# PC_JTAGInterface.net
KiCad netlist of a schematic drawn in Altium Designer
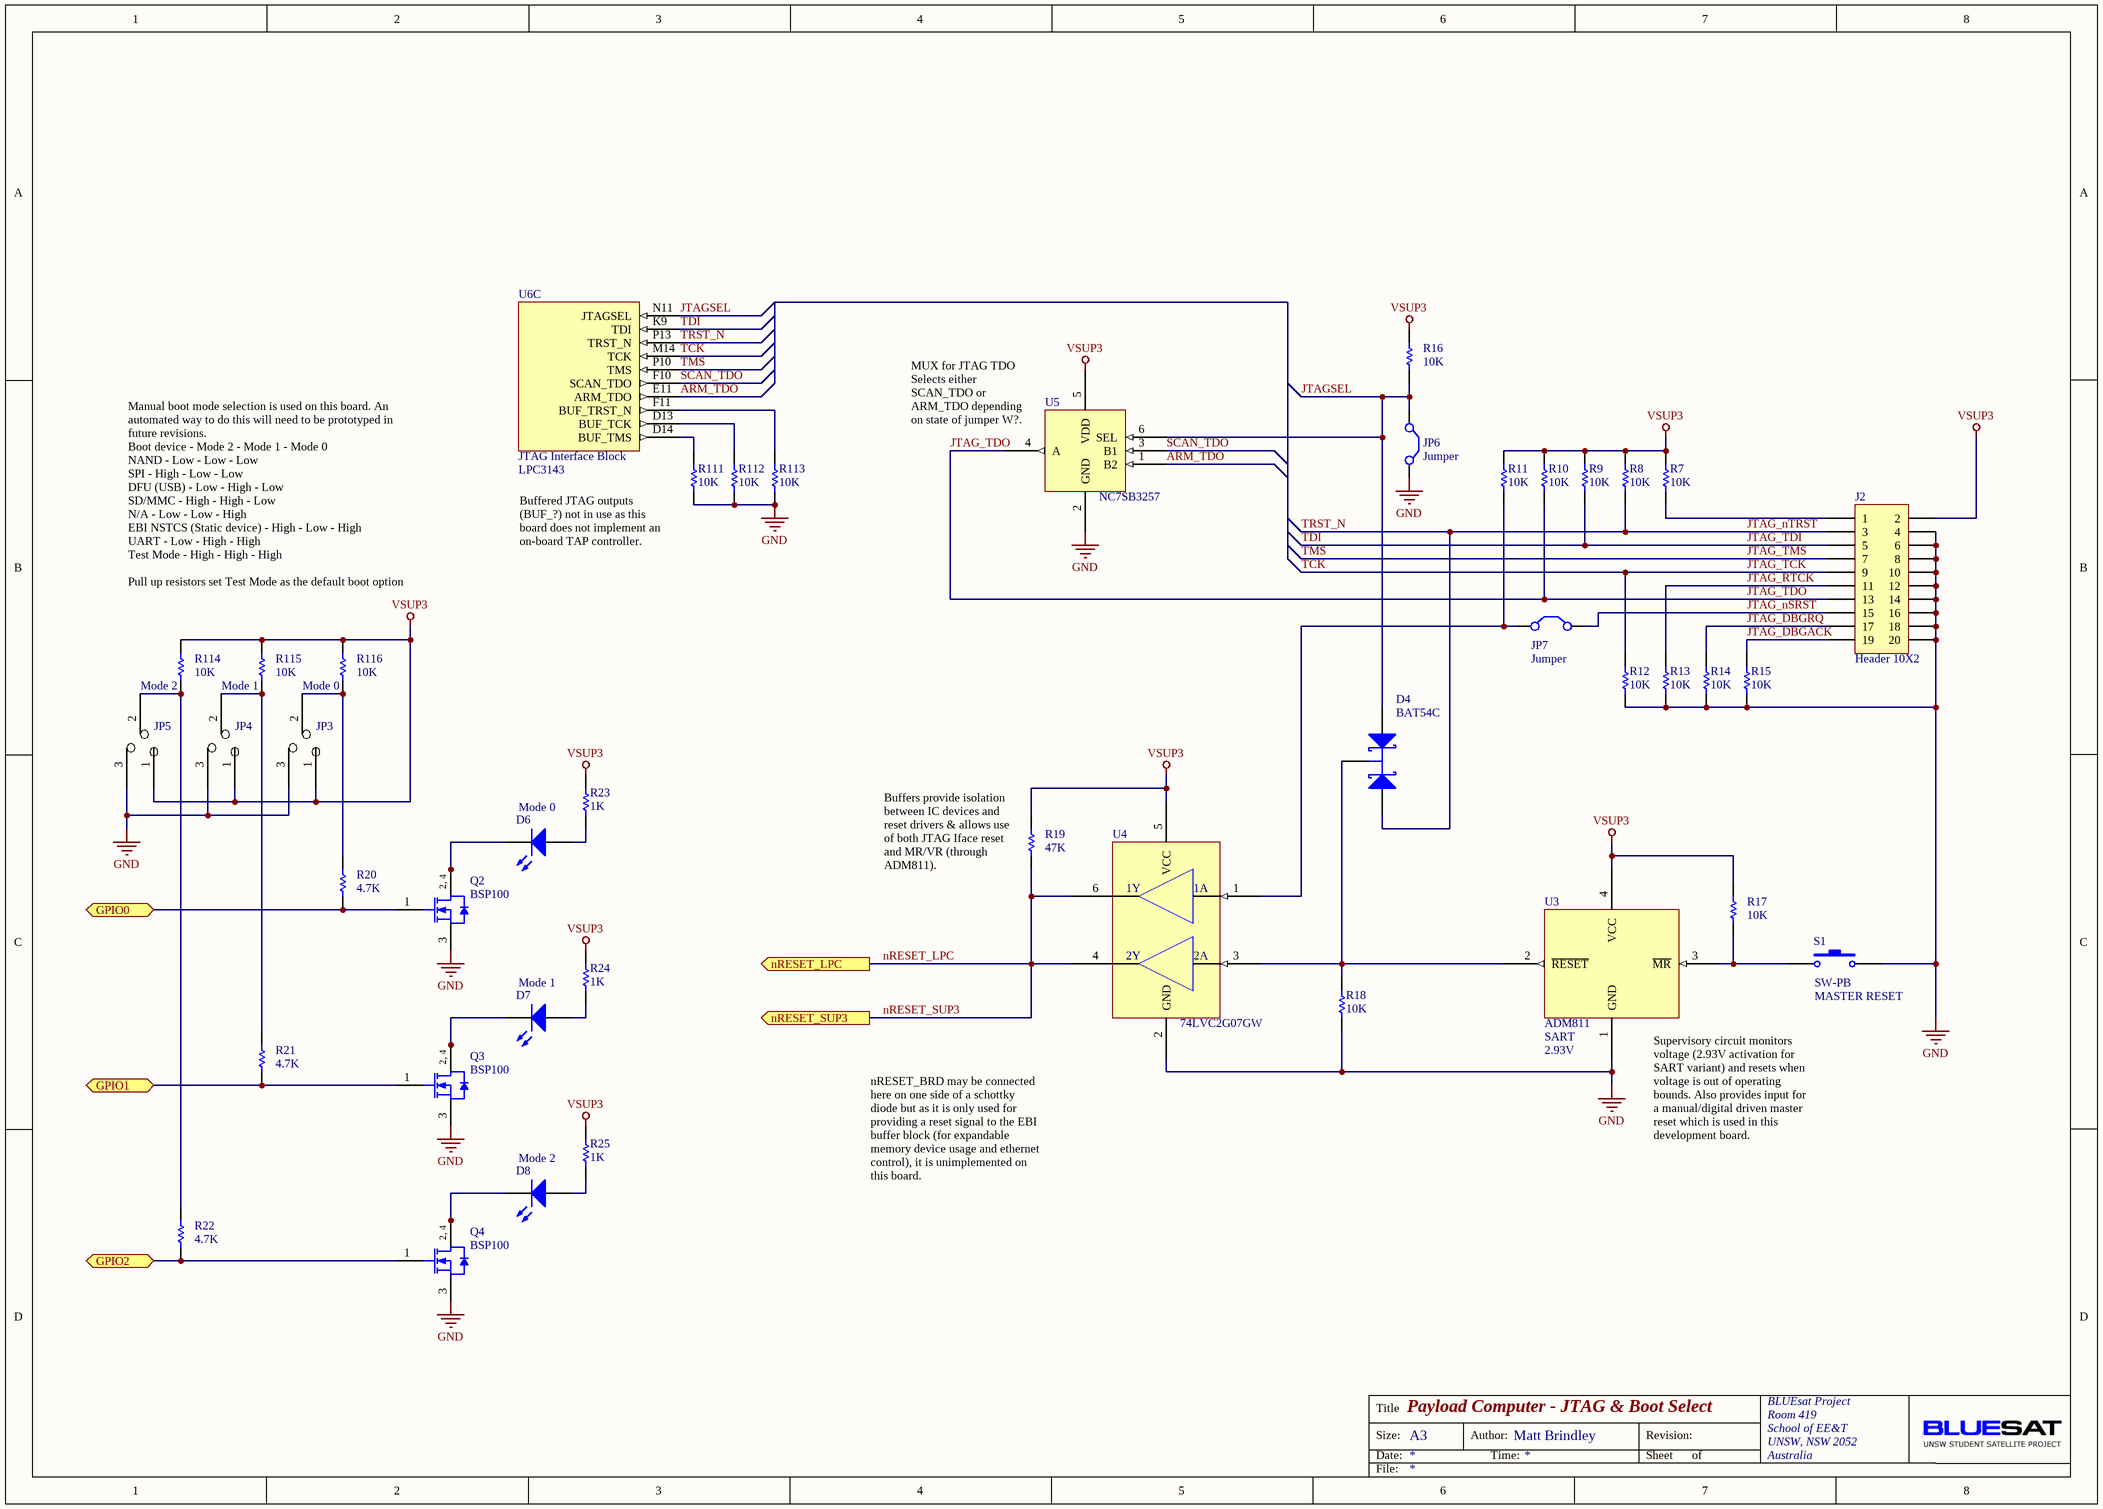
[diagram p0: PC_JTAGInterface.SchDoc]

(export (version "E")
  (design (tool "Eeschema 10.0.6"))
  (components
    (comp (ref "D4")
      (value "BAT54C")
      (footprint "SOT23_N")
      (description "Schottky Barrier Double Diode")
      (fields (field (name "PUBLISHER") "Altium Limited"))
      (libsource (lib "Philips Discrete Diode - Schottky") (part "BAT54C"))
    )
    (comp (ref "D6")
      (value "LED2")
      (footprint "DSO-F2/D6.1")
      (description "Typical RED, GREEN, YELLOW, AMBER GaAs LED")
      (fields (field (name "PUBLISHER") "Altium Limited"))
      (libsource (lib "Miscellaneous Devices") (part "LED2"))
    )
    (comp (ref "D7")
      (value "LED2")
      (footprint "DSO-F2/D6.1")
      (description "Typical RED, GREEN, YELLOW, AMBER GaAs LED")
      (fields (field (name "PUBLISHER") "Altium Limited"))
      (libsource (lib "Miscellaneous Devices") (part "LED2"))
    )
    (comp (ref "D8")
      (value "LED2")
      (footprint "DSO-F2/D6.1")
      (description "Typical RED, GREEN, YELLOW, AMBER GaAs LED")
      (fields (field (name "PUBLISHER") "Altium Limited"))
      (libsource (lib "Miscellaneous Devices") (part "LED2"))
    )
    (comp (ref "J2")
      (value "Header 10X2")
      (footprint "HDR2X10")
      (description "Header, 10-Pin, Dual row")
      (fields (field (name "PUBLISHER") "Altium Limited"))
      (libsource (lib "Miscellaneous Connectors") (part "Header 10X2"))
    )
    (comp (ref "JP3")
      (value "Jumper")
      (footprint "HDR1X3")
      (description "3 pin jumper for selection")
      (fields (field (name "PUBLISHER") "Altium Limited"))
      (libsource (lib "PC_Components") (part "2 position jumper"))
    )
    (comp (ref "JP4")
      (value "Jumper")
      (footprint "HDR1X3")
      (description "3 pin jumper for selection")
      (fields (field (name "PUBLISHER") "Altium Limited"))
      (libsource (lib "PC_Components") (part "2 position jumper"))
    )
    (comp (ref "JP5")
      (value "Jumper")
      (footprint "HDR1X3")
      (description "3 pin jumper for selection")
      (fields (field (name "PUBLISHER") "Altium Limited"))
      (libsource (lib "PC_Components") (part "2 position jumper"))
    )
    (comp (ref "JP6")
      (value "Jumper")
      (footprint "HDR1X2")
      (description "Jumper Wire")
      (fields (field (name "PUBLISHER") "Altium Limited"))
      (libsource (lib "Miscellaneous Devices") (part "Jumper"))
    )
    (comp (ref "JP7")
      (value "Jumper")
      (footprint "HDR1X2")
      (description "Jumper Wire")
      (fields (field (name "PUBLISHER") "Altium Limited"))
      (libsource (lib "Miscellaneous Devices") (part "Jumper"))
    )
    (comp (ref "Q2")
      (value "BSP100")
      (footprint "SOT223_N")
      (description "N-channel Enhancement Mode MOSFET")
      (fields (field (name "PUBLISHER") "Altium Limited"))
      (libsource (lib "Philips Discrete MOSFET - Power") (part "BSP100"))
    )
    (comp (ref "Q3")
      (value "BSP100")
      (footprint "SOT223_N")
      (description "N-channel Enhancement Mode MOSFET")
      (fields (field (name "PUBLISHER") "Altium Limited"))
      (libsource (lib "Philips Discrete MOSFET - Power") (part "BSP100"))
    )
    (comp (ref "Q4")
      (value "BSP100")
      (footprint "SOT223_N")
      (description "N-channel Enhancement Mode MOSFET")
      (fields (field (name "PUBLISHER") "Altium Limited"))
      (libsource (lib "Philips Discrete MOSFET - Power") (part "BSP100"))
    )
    (comp (ref "R7")
      (value "10K")
      (footprint "6-0805_L")
      (description "Semiconductor Resistor")
      (fields (field (name "Comment") "Res Semi") (field (name "PUBLISHER") "Altium Limited"))
      (libsource (lib "Miscellaneous Devices") (part "Res Semi"))
    )
    (comp (ref "R8")
      (value "10K")
      (footprint "6-0805_L")
      (description "Semiconductor Resistor")
      (fields (field (name "Comment") "Res Semi") (field (name "PUBLISHER") "Altium Limited"))
      (libsource (lib "Miscellaneous Devices") (part "Res Semi"))
    )
    (comp (ref "R9")
      (value "10K")
      (footprint "6-0805_L")
      (description "Semiconductor Resistor")
      (fields (field (name "Comment") "Res Semi") (field (name "PUBLISHER") "Altium Limited"))
      (libsource (lib "Miscellaneous Devices") (part "Res Semi"))
    )
    (comp (ref "R10")
      (value "10K")
      (footprint "6-0805_L")
      (description "Semiconductor Resistor")
      (fields (field (name "Comment") "Res Semi") (field (name "PUBLISHER") "Altium Limited"))
      (libsource (lib "Miscellaneous Devices") (part "Res Semi"))
    )
    (comp (ref "R11")
      (value "10K")
      (footprint "6-0805_L")
      (description "Semiconductor Resistor")
      (fields (field (name "Comment") "Res Semi") (field (name "PUBLISHER") "Altium Limited"))
      (libsource (lib "Miscellaneous Devices") (part "Res Semi"))
    )
    (comp (ref "R12")
      (value "10K")
      (footprint "6-0805_L")
      (description "Semiconductor Resistor")
      (fields (field (name "Comment") "Res Semi") (field (name "PUBLISHER") "Altium Limited"))
      (libsource (lib "Miscellaneous Devices") (part "Res Semi"))
    )
    (comp (ref "R13")
      (value "10K")
      (footprint "6-0805_L")
      (description "Semiconductor Resistor")
      (fields (field (name "Comment") "Res Semi") (field (name "PUBLISHER") "Altium Limited"))
      (libsource (lib "Miscellaneous Devices") (part "Res Semi"))
    )
    (comp (ref "R14")
      (value "10K")
      (footprint "6-0805_L")
      (description "Semiconductor Resistor")
      (fields (field (name "Comment") "Res Semi") (field (name "PUBLISHER") "Altium Limited"))
      (libsource (lib "Miscellaneous Devices") (part "Res Semi"))
    )
    (comp (ref "R15")
      (value "10K")
      (footprint "6-0805_L")
      (description "Semiconductor Resistor")
      (fields (field (name "Comment") "Res Semi") (field (name "PUBLISHER") "Altium Limited"))
      (libsource (lib "Miscellaneous Devices") (part "Res Semi"))
    )
    (comp (ref "R16")
      (value "10K")
      (footprint "6-0805_L")
      (description "Semiconductor Resistor")
      (fields (field (name "Comment") "Res Semi") (field (name "PUBLISHER") "Altium Limited"))
      (libsource (lib "Miscellaneous Devices") (part "Res Semi"))
    )
    (comp (ref "R17")
      (value "10K")
      (footprint "6-0805_L")
      (description "Semiconductor Resistor")
      (fields (field (name "Comment") "Res Semi") (field (name "PUBLISHER") "Altium Limited"))
      (libsource (lib "Miscellaneous Devices") (part "Res Semi"))
    )
    (comp (ref "R18")
      (value "10K")
      (footprint "6-0805_L")
      (description "Semiconductor Resistor")
      (fields (field (name "Comment") "Res Semi") (field (name "PUBLISHER") "Altium Limited"))
      (libsource (lib "Miscellaneous Devices") (part "Res Semi"))
    )
    (comp (ref "R19")
      (value "47K")
      (footprint "6-0805_L")
      (description "Semiconductor Resistor")
      (fields (field (name "Comment") "Res Semi") (field (name "PUBLISHER") "Altium Limited"))
      (libsource (lib "Miscellaneous Devices") (part "Res Semi"))
    )
    (comp (ref "R20")
      (value "4.7K")
      (footprint "6-0805_L")
      (description "Semiconductor Resistor")
      (fields (field (name "Comment") "Res Semi") (field (name "PUBLISHER") "Altium Limited"))
      (libsource (lib "Miscellaneous Devices") (part "Res Semi"))
    )
    (comp (ref "R21")
      (value "4.7K")
      (footprint "6-0805_L")
      (description "Semiconductor Resistor")
      (fields (field (name "Comment") "Res Semi") (field (name "PUBLISHER") "Altium Limited"))
      (libsource (lib "Miscellaneous Devices") (part "Res Semi"))
    )
    (comp (ref "R22")
      (value "4.7K")
      (footprint "6-0805_L")
      (description "Semiconductor Resistor")
      (fields (field (name "Comment") "Res Semi") (field (name "PUBLISHER") "Altium Limited"))
      (libsource (lib "Miscellaneous Devices") (part "Res Semi"))
    )
    (comp (ref "R23")
      (value "1K")
      (footprint "6-0805_L")
      (description "Semiconductor Resistor")
      (fields (field (name "Comment") "Res Semi") (field (name "PUBLISHER") "Altium Limited"))
      (libsource (lib "Miscellaneous Devices") (part "Res Semi"))
    )
    (comp (ref "R24")
      (value "1K")
      (footprint "6-0805_L")
      (description "Semiconductor Resistor")
      (fields (field (name "Comment") "Res Semi") (field (name "PUBLISHER") "Altium Limited"))
      (libsource (lib "Miscellaneous Devices") (part "Res Semi"))
    )
    (comp (ref "R25")
      (value "1K")
      (footprint "6-0805_L")
      (description "Semiconductor Resistor")
      (fields (field (name "Comment") "Res Semi") (field (name "PUBLISHER") "Altium Limited"))
      (libsource (lib "Miscellaneous Devices") (part "Res Semi"))
    )
    (comp (ref "R111")
      (value "10K")
      (footprint "6-0805_L")
      (description "Semiconductor Resistor")
      (fields (field (name "Comment") "Res Semi") (field (name "PUBLISHER") "Altium Limited"))
      (libsource (lib "Miscellaneous Devices") (part "Res Semi"))
    )
    (comp (ref "R112")
      (value "10K")
      (footprint "6-0805_L")
      (description "Semiconductor Resistor")
      (fields (field (name "Comment") "Res Semi") (field (name "PUBLISHER") "Altium Limited"))
      (libsource (lib "Miscellaneous Devices") (part "Res Semi"))
    )
    (comp (ref "R113")
      (value "10K")
      (footprint "6-0805_L")
      (description "Semiconductor Resistor")
      (fields (field (name "Comment") "Res Semi") (field (name "PUBLISHER") "Altium Limited"))
      (libsource (lib "Miscellaneous Devices") (part "Res Semi"))
    )
    (comp (ref "R114")
      (value "10K")
      (footprint "6-0805_L")
      (description "Semiconductor Resistor")
      (fields (field (name "Comment") "Res Semi") (field (name "PUBLISHER") "Altium Limited"))
      (libsource (lib "Miscellaneous Devices") (part "Res Semi"))
    )
    (comp (ref "R115")
      (value "10K")
      (footprint "6-0805_L")
      (description "Semiconductor Resistor")
      (fields (field (name "Comment") "Res Semi") (field (name "PUBLISHER") "Altium Limited"))
      (libsource (lib "Miscellaneous Devices") (part "Res Semi"))
    )
    (comp (ref "R116")
      (value "10K")
      (footprint "6-0805_L")
      (description "Semiconductor Resistor")
      (fields (field (name "Comment") "Res Semi") (field (name "PUBLISHER") "Altium Limited"))
      (libsource (lib "Miscellaneous Devices") (part "Res Semi"))
    )
    (comp (ref "S1")
      (value "SW-PB")
      (footprint "SPST-2")
      (description "Switch")
      (fields (field (name "PUBLISHER") "Altium Limited"))
      (libsource (lib "Miscellaneous Devices") (part "SW-PB"))
    )
    (comp (ref "U3")
      (value "ADM811")
      (footprint "SOT190P230X102-4N")
      (description "Supervisory Circuit")
      (fields (field (name "PUBLISHER") "Altium Limited"))
      (libsource (lib "PC_Components") (part "ADM811"))
    )
    (comp (ref "U4")
      (value "74LVC2G07GW")
      (footprint "SOT65P210X110-6M")
      (description "Non-inverting buffers with open-drain outputs")
      (fields (field (name "PUBLISHER") "Altium Limited"))
      (libsource (lib "PC_Components") (part "74LVC2G07GW"))
    )
    (comp (ref "U5")
      (value "NC7SB3257")
      (footprint "TSOP65P210X110-6N")
      (description "2:1 Mux, Fairchild")
      (fields (field (name "PUBLISHER") "Altium Limited"))
      (libsource (lib "PC_Components") (part "NC7SB3257"))
    )
    (comp (ref "U6")
      (value "LPC3143")
      (footprint "PC_Footprints:BGA180C80P14X14_1200X1200X120")
      (description "NXP ARM9 based microcontroller")
      (fields (field (name "PUBLISHER") "BLUEsat Project"))
      (libsource (lib "PC_Components") (part "LPC3143"))
    )
  )
  (nets
    (net (code "1") (name "/ARM_TDO") (class "Default")
      (node (ref "U5") (pin "1") (pinfunction "B2_1") (pintype "input"))
      (node (ref "U6") (pin "E11") (pinfunction "ARM_TDO_E11") (pintype "output"))
    )
    (net (code "2") (name "/GPIO0") (class "Default")
      (node (ref "Q2") (pin "1") (pinfunction "G_1") (pintype "passive"))
      (node (ref "R20") (pin "1") (pinfunction "1_1") (pintype "passive"))
    )
    (net (code "3") (name "/GPIO1") (class "Default")
      (node (ref "Q3") (pin "1") (pinfunction "G_1") (pintype "passive"))
      (node (ref "R21") (pin "1") (pinfunction "1_1") (pintype "passive"))
    )
    (net (code "4") (name "/GPIO2") (class "Default")
      (node (ref "Q4") (pin "1") (pinfunction "G_1") (pintype "passive"))
      (node (ref "R22") (pin "1") (pinfunction "1_1") (pintype "passive"))
    )
    (net (code "5") (name "/JTAGSEL") (class "Default")
      (node (ref "D4") (pin "2") (pinfunction "A2_2") (pintype "passive"))
      (node (ref "JP6") (pin "1") (pinfunction "C1_1") (pintype "passive"))
      (node (ref "R16") (pin "1") (pinfunction "1_1") (pintype "passive"))
      (node (ref "U5") (pin "6") (pinfunction "SEL_6") (pintype "input"))
      (node (ref "U6") (pin "N11") (pinfunction "JTAGSEL_N11") (pintype "input"))
    )
    (net (code "6") (name "/JTAG_DBGACK") (class "Default")
      (node (ref "J2") (pin "19") (pinfunction "19_19") (pintype "passive"))
      (node (ref "R15") (pin "2") (pinfunction "2_2") (pintype "passive"))
    )
    (net (code "7") (name "/JTAG_DBGRQ") (class "Default")
      (node (ref "J2") (pin "17") (pinfunction "17_17") (pintype "passive"))
      (node (ref "R14") (pin "2") (pinfunction "2_2") (pintype "passive"))
    )
    (net (code "8") (name "/JTAG_RTCK") (class "Default")
      (node (ref "J2") (pin "11") (pinfunction "11_11") (pintype "passive"))
      (node (ref "R13") (pin "2") (pinfunction "2_2") (pintype "passive"))
    )
    (net (code "9") (name "/JTAG_TCK") (class "Default")
      (node (ref "J2") (pin "9") (pinfunction "9_9") (pintype "passive"))
      (node (ref "R12") (pin "2") (pinfunction "2_2") (pintype "passive"))
      (node (ref "U6") (pin "M14") (pinfunction "TCK_M14") (pintype "input"))
    )
    (net (code "10") (name "/JTAG_TDI") (class "Default")
      (node (ref "J2") (pin "5") (pinfunction "5_5") (pintype "passive"))
      (node (ref "R9") (pin "1") (pinfunction "1_1") (pintype "passive"))
      (node (ref "U6") (pin "K9") (pinfunction "TDI_K9") (pintype "input"))
    )
    (net (code "11") (name "/JTAG_TDO") (class "Default")
      (node (ref "J2") (pin "13") (pinfunction "13_13") (pintype "passive"))
      (node (ref "R10") (pin "1") (pinfunction "1_1") (pintype "passive"))
      (node (ref "U5") (pin "4") (pinfunction "A_4") (pintype "output"))
    )
    (net (code "12") (name "/JTAG_TMS") (class "Default")
      (node (ref "J2") (pin "7") (pinfunction "7_7") (pintype "passive"))
      (node (ref "U6") (pin "P10") (pinfunction "TMS_P10") (pintype "input"))
    )
    (net (code "13") (name "/JTAG_nSRST") (class "Default")
      (node (ref "J2") (pin "15") (pinfunction "15_15") (pintype "passive"))
      (node (ref "JP7") (pin "2") (pinfunction "C2_2") (pintype "passive"))
    )
    (net (code "14") (name "/JTAG_nTRST") (class "Default")
      (node (ref "D4") (pin "1") (pinfunction "A1_1") (pintype "passive"))
      (node (ref "J2") (pin "3") (pinfunction "3_3") (pintype "passive"))
      (node (ref "R8") (pin "1") (pinfunction "1_1") (pintype "passive"))
      (node (ref "U6") (pin "P13") (pinfunction "TRST_N_P13") (pintype "input"))
    )
    (net (code "15") (name "/SCAN_TDO") (class "Default")
      (node (ref "U5") (pin "3") (pinfunction "B1_3") (pintype "input"))
      (node (ref "U6") (pin "F10") (pinfunction "SCAN_TDO_F10") (pintype "output"))
    )
    (net (code "16") (name "/nRESET_LPC") (class "Default")
      (node (ref "R19") (pin "1") (pinfunction "1_1") (pintype "passive"))
      (node (ref "U4") (pin "4") (pinfunction "2Y_4") (pintype "tri_state"))
      (node (ref "U4") (pin "6") (pinfunction "1Y_6") (pintype "tri_state"))
    )
    (net (code "17") (name "GND") (class "Default")
      (node (ref "J2") (pin "10") (pinfunction "10_10") (pintype "passive"))
      (node (ref "J2") (pin "12") (pinfunction "12_12") (pintype "passive"))
      (node (ref "J2") (pin "14") (pinfunction "14_14") (pintype "passive"))
      (node (ref "J2") (pin "16") (pinfunction "16_16") (pintype "passive"))
      (node (ref "J2") (pin "18") (pinfunction "18_18") (pintype "passive"))
      (node (ref "J2") (pin "20") (pinfunction "20_20") (pintype "passive"))
      (node (ref "J2") (pin "4") (pinfunction "4_4") (pintype "passive"))
      (node (ref "J2") (pin "6") (pinfunction "6_6") (pintype "passive"))
      (node (ref "J2") (pin "8") (pinfunction "8_8") (pintype "passive"))
      (node (ref "JP3") (pin "3") (pinfunction "3_3") (pintype "passive"))
      (node (ref "JP4") (pin "3") (pinfunction "3_3") (pintype "passive"))
      (node (ref "JP5") (pin "3") (pinfunction "3_3") (pintype "passive"))
      (node (ref "JP6") (pin "2") (pinfunction "C2_2") (pintype "passive"))
      (node (ref "Q2") (pin "3") (pinfunction "S_3") (pintype "passive"))
      (node (ref "Q3") (pin "3") (pinfunction "S_3") (pintype "passive"))
      (node (ref "Q4") (pin "3") (pinfunction "S_3") (pintype "passive"))
      (node (ref "R111") (pin "1") (pinfunction "1_1") (pintype "passive"))
      (node (ref "R112") (pin "1") (pinfunction "1_1") (pintype "passive"))
      (node (ref "R113") (pin "1") (pinfunction "1_1") (pintype "passive"))
      (node (ref "R12") (pin "1") (pinfunction "1_1") (pintype "passive"))
      (node (ref "R13") (pin "1") (pinfunction "1_1") (pintype "passive"))
      (node (ref "R14") (pin "1") (pinfunction "1_1") (pintype "passive"))
      (node (ref "R15") (pin "1") (pinfunction "1_1") (pintype "passive"))
      (node (ref "R18") (pin "1") (pinfunction "1_1") (pintype "passive"))
      (node (ref "S1") (pin "2") (pinfunction "2_2") (pintype "passive"))
      (node (ref "U3") (pin "1") (pinfunction "GND_1") (pintype "power_in"))
      (node (ref "U4") (pin "2") (pinfunction "GND_2") (pintype "power_in"))
      (node (ref "U5") (pin "2") (pinfunction "GND_2") (pintype "power_in"))
    )
    (net (code "18") (name "Net-(D4-K)") (class "Default")
      (node (ref "D4") (pin "3") (pinfunction "K_3") (pintype "passive"))
      (node (ref "R18") (pin "2") (pinfunction "2_2") (pintype "passive"))
      (node (ref "U3") (pin "2") (pinfunction "~{RESET}_2") (pintype "output"))
      (node (ref "U4") (pin "3") (pinfunction "2A_3") (pintype "input"))
    )
    (net (code "19") (name "Net-(D6-A)") (class "Default")
      (node (ref "D6") (pin "1") (pinfunction "A_1") (pintype "passive"))
      (node (ref "R23") (pin "1") (pinfunction "1_1") (pintype "passive"))
    )
    (net (code "20") (name "Net-(D6-K)") (class "Default")
      (node (ref "D6") (pin "2") (pinfunction "K_2") (pintype "passive"))
      (node (ref "Q2") (pin "2") (pinfunction "D_2") (pintype "passive"))
      (node (ref "Q2") (pin "4") (pinfunction "D_4") (pintype "passive"))
    )
    (net (code "21") (name "Net-(D7-A)") (class "Default")
      (node (ref "D7") (pin "1") (pinfunction "A_1") (pintype "passive"))
      (node (ref "R24") (pin "1") (pinfunction "1_1") (pintype "passive"))
    )
    (net (code "22") (name "Net-(D7-K)") (class "Default")
      (node (ref "D7") (pin "2") (pinfunction "K_2") (pintype "passive"))
      (node (ref "Q3") (pin "2") (pinfunction "D_2") (pintype "passive"))
      (node (ref "Q3") (pin "4") (pinfunction "D_4") (pintype "passive"))
    )
    (net (code "23") (name "Net-(D8-A)") (class "Default")
      (node (ref "D8") (pin "1") (pinfunction "A_1") (pintype "passive"))
      (node (ref "R25") (pin "1") (pinfunction "1_1") (pintype "passive"))
    )
    (net (code "24") (name "Net-(D8-K)") (class "Default")
      (node (ref "D8") (pin "2") (pinfunction "K_2") (pintype "passive"))
      (node (ref "Q4") (pin "2") (pinfunction "D_2") (pintype "passive"))
      (node (ref "Q4") (pin "4") (pinfunction "D_4") (pintype "passive"))
    )
    (net (code "25") (name "Net-(J2-Pad1)") (class "Default")
      (node (ref "J2") (pin "1") (pinfunction "1_1") (pintype "passive"))
      (node (ref "R7") (pin "1") (pinfunction "1_1") (pintype "passive"))
    )
    (net (code "26") (name "Net-(JP3-Pad2)") (class "Default")
      (node (ref "JP3") (pin "2") (pinfunction "2_2") (pintype "passive"))
      (node (ref "R116") (pin "1") (pinfunction "1_1") (pintype "passive"))
      (node (ref "R20") (pin "2") (pinfunction "2_2") (pintype "passive"))
    )
    (net (code "27") (name "Net-(JP4-Pad2)") (class "Default")
      (node (ref "JP4") (pin "2") (pinfunction "2_2") (pintype "passive"))
      (node (ref "R115") (pin "1") (pinfunction "1_1") (pintype "passive"))
      (node (ref "R21") (pin "2") (pinfunction "2_2") (pintype "passive"))
    )
    (net (code "28") (name "Net-(JP5-Pad2)") (class "Default")
      (node (ref "JP5") (pin "2") (pinfunction "2_2") (pintype "passive"))
      (node (ref "R114") (pin "1") (pinfunction "1_1") (pintype "passive"))
      (node (ref "R22") (pin "2") (pinfunction "2_2") (pintype "passive"))
    )
    (net (code "29") (name "Net-(JP7-C1)") (class "Default")
      (node (ref "JP7") (pin "1") (pinfunction "C1_1") (pintype "passive"))
      (node (ref "R11") (pin "1") (pinfunction "1_1") (pintype "passive"))
      (node (ref "U4") (pin "1") (pinfunction "1A_1") (pintype "input"))
    )
    (net (code "30") (name "Net-(U3-~{MR})") (class "Default")
      (node (ref "R17") (pin "1") (pinfunction "1_1") (pintype "passive"))
      (node (ref "S1") (pin "1") (pinfunction "1_1") (pintype "passive"))
      (node (ref "U3") (pin "3") (pinfunction "~{MR}_3") (pintype "input"))
    )
    (net (code "31") (name "Net-(U6C-BUF_TCK)") (class "Default")
      (node (ref "R112") (pin "2") (pinfunction "2_2") (pintype "passive"))
      (node (ref "U6") (pin "D13") (pinfunction "BUF_TCK_D13") (pintype "output"))
    )
    (net (code "32") (name "Net-(U6C-BUF_TMS)") (class "Default")
      (node (ref "R111") (pin "2") (pinfunction "2_2") (pintype "passive"))
      (node (ref "U6") (pin "D14") (pinfunction "BUF_TMS_D14") (pintype "output"))
    )
    (net (code "33") (name "Net-(U6C-BUF_TRST_N)") (class "Default")
      (node (ref "R113") (pin "2") (pinfunction "2_2") (pintype "passive"))
      (node (ref "U6") (pin "F11") (pinfunction "BUF_TRST_N_F11") (pintype "output"))
    )
    (net (code "34") (name "VSUP3") (class "Default")
      (node (ref "J2") (pin "2") (pinfunction "2_2") (pintype "passive"))
      (node (ref "JP3") (pin "1") (pinfunction "1_1") (pintype "passive"))
      (node (ref "JP4") (pin "1") (pinfunction "1_1") (pintype "passive"))
      (node (ref "JP5") (pin "1") (pinfunction "1_1") (pintype "passive"))
      (node (ref "R10") (pin "2") (pinfunction "2_2") (pintype "passive"))
      (node (ref "R11") (pin "2") (pinfunction "2_2") (pintype "passive"))
      (node (ref "R114") (pin "2") (pinfunction "2_2") (pintype "passive"))
      (node (ref "R115") (pin "2") (pinfunction "2_2") (pintype "passive"))
      (node (ref "R116") (pin "2") (pinfunction "2_2") (pintype "passive"))
      (node (ref "R16") (pin "2") (pinfunction "2_2") (pintype "passive"))
      (node (ref "R17") (pin "2") (pinfunction "2_2") (pintype "passive"))
      (node (ref "R19") (pin "2") (pinfunction "2_2") (pintype "passive"))
      (node (ref "R23") (pin "2") (pinfunction "2_2") (pintype "passive"))
      (node (ref "R24") (pin "2") (pinfunction "2_2") (pintype "passive"))
      (node (ref "R25") (pin "2") (pinfunction "2_2") (pintype "passive"))
      (node (ref "R7") (pin "2") (pinfunction "2_2") (pintype "passive"))
      (node (ref "R8") (pin "2") (pinfunction "2_2") (pintype "passive"))
      (node (ref "R9") (pin "2") (pinfunction "2_2") (pintype "passive"))
      (node (ref "U3") (pin "4") (pinfunction "VCC_4") (pintype "power_in"))
      (node (ref "U4") (pin "5") (pinfunction "VCC_5") (pintype "power_in"))
      (node (ref "U5") (pin "5") (pinfunction "VDD_5") (pintype "power_in"))
    )
  )
)
